# main_pcb.net
KiCad netlist of a schematic drawn in EAGLE
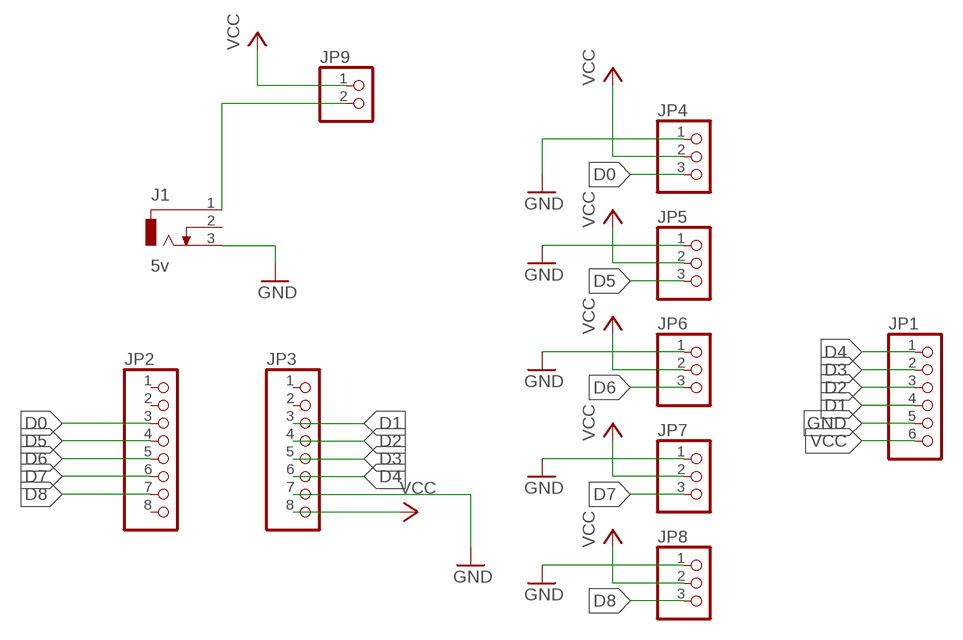
[diagram p0: schematic, sheet 1]

(export (version "E")
  (design (tool "Eeschema 10.0.6"))
  (components
    (comp (ref "J1")
      (value "5v")
      (footprint "eagle-import:DCJ0303")
      (libsource (lib "eagle-import") (part "DCJ0303"))
    )
    (comp (ref "JP1")
      (value "PINHD-1X6")
      (footprint "eagle-import:1X06")
      (libsource (lib "eagle-import") (part "PINHD-1X6"))
    )
    (comp (ref "JP2")
      (value "PINHD-1X8")
      (footprint "eagle-import:1X08")
      (libsource (lib "eagle-import") (part "PINHD-1X8"))
    )
    (comp (ref "JP3")
      (value "PINHD-1X8")
      (footprint "eagle-import:1X08")
      (libsource (lib "eagle-import") (part "PINHD-1X8"))
    )
    (comp (ref "JP4")
      (value "PINHD-1X3")
      (footprint "eagle-import:1X03")
      (libsource (lib "eagle-import") (part "PINHD-1X3"))
    )
    (comp (ref "JP5")
      (value "PINHD-1X3")
      (footprint "eagle-import:1X03")
      (libsource (lib "eagle-import") (part "PINHD-1X3"))
    )
    (comp (ref "JP6")
      (value "PINHD-1X3")
      (footprint "eagle-import:1X03")
      (libsource (lib "eagle-import") (part "PINHD-1X3"))
    )
    (comp (ref "JP7")
      (value "PINHD-1X3")
      (footprint "eagle-import:1X03")
      (libsource (lib "eagle-import") (part "PINHD-1X3"))
    )
    (comp (ref "JP8")
      (value "PINHD-1X3")
      (footprint "eagle-import:1X03")
      (libsource (lib "eagle-import") (part "PINHD-1X3"))
    )
    (comp (ref "JP9")
      (value "PINHD-1X2")
      (footprint "eagle-import:1X02")
      (libsource (lib "eagle-import") (part "PINHD-1X2"))
    )
  )
  (nets
    (net (code "1") (name "D0") (class "Default")
      (node (ref "JP2") (pin "3") (pinfunction "3_3") (pintype "passive"))
      (node (ref "JP4") (pin "3") (pinfunction "3_3") (pintype "passive"))
    )
    (net (code "2") (name "D1") (class "Default")
      (node (ref "JP1") (pin "4") (pinfunction "4_4") (pintype "passive"))
      (node (ref "JP3") (pin "3") (pinfunction "3_3") (pintype "passive"))
    )
    (net (code "3") (name "D2") (class "Default")
      (node (ref "JP1") (pin "3") (pinfunction "3_3") (pintype "passive"))
      (node (ref "JP3") (pin "4") (pinfunction "4_4") (pintype "passive"))
    )
    (net (code "4") (name "D3") (class "Default")
      (node (ref "JP1") (pin "2") (pinfunction "2_2") (pintype "passive"))
      (node (ref "JP3") (pin "5") (pinfunction "5_5") (pintype "passive"))
    )
    (net (code "5") (name "D4") (class "Default")
      (node (ref "JP1") (pin "1") (pinfunction "1_1") (pintype "passive"))
      (node (ref "JP3") (pin "6") (pinfunction "6_6") (pintype "passive"))
    )
    (net (code "6") (name "D5") (class "Default")
      (node (ref "JP2") (pin "4") (pinfunction "4_4") (pintype "passive"))
      (node (ref "JP5") (pin "3") (pinfunction "3_3") (pintype "passive"))
    )
    (net (code "7") (name "D6") (class "Default")
      (node (ref "JP2") (pin "5") (pinfunction "5_5") (pintype "passive"))
      (node (ref "JP6") (pin "3") (pinfunction "3_3") (pintype "passive"))
    )
    (net (code "8") (name "D7") (class "Default")
      (node (ref "JP2") (pin "6") (pinfunction "6_6") (pintype "passive"))
      (node (ref "JP7") (pin "3") (pinfunction "3_3") (pintype "passive"))
    )
    (net (code "9") (name "D8") (class "Default")
      (node (ref "JP2") (pin "7") (pinfunction "7_7") (pintype "passive"))
      (node (ref "JP8") (pin "3") (pinfunction "3_3") (pintype "passive"))
    )
    (net (code "10") (name "GND") (class "Default")
      (node (ref "J1") (pin "3") (pinfunction "3_3") (pintype "passive"))
      (node (ref "JP1") (pin "5") (pinfunction "5_5") (pintype "passive"))
      (node (ref "JP3") (pin "7") (pinfunction "7_7") (pintype "passive"))
      (node (ref "JP4") (pin "1") (pinfunction "1_1") (pintype "passive"))
      (node (ref "JP5") (pin "1") (pinfunction "1_1") (pintype "passive"))
      (node (ref "JP6") (pin "1") (pinfunction "1_1") (pintype "passive"))
      (node (ref "JP7") (pin "1") (pinfunction "1_1") (pintype "passive"))
      (node (ref "JP8") (pin "1") (pinfunction "1_1") (pintype "passive"))
    )
    (net (code "11") (name "Net-(J1-Pad1)") (class "Default")
      (node (ref "J1") (pin "1") (pinfunction "1_1") (pintype "passive"))
      (node (ref "JP9") (pin "2") (pinfunction "2_2") (pintype "passive"))
    )
    (net (code "12") (name "VCC") (class "Default")
      (node (ref "JP1") (pin "6") (pinfunction "6_6") (pintype "passive"))
      (node (ref "JP3") (pin "8") (pinfunction "8_8") (pintype "passive"))
      (node (ref "JP4") (pin "2") (pinfunction "2_2") (pintype "passive"))
      (node (ref "JP5") (pin "2") (pinfunction "2_2") (pintype "passive"))
      (node (ref "JP6") (pin "2") (pinfunction "2_2") (pintype "passive"))
      (node (ref "JP7") (pin "2") (pinfunction "2_2") (pintype "passive"))
      (node (ref "JP8") (pin "2") (pinfunction "2_2") (pintype "passive"))
      (node (ref "JP9") (pin "1") (pinfunction "1_1") (pintype "passive"))
    )
    (net (code "13") (name "unconnected-(J1-Pad2)") (class "Default")
      (node (ref "J1") (pin "2") (pinfunction "2_2") (pintype "passive"))
    )
    (net (code "14") (name "unconnected-(JP2-Pad1)") (class "Default")
      (node (ref "JP2") (pin "1") (pinfunction "1_1") (pintype "passive"))
    )
    (net (code "15") (name "unconnected-(JP2-Pad2)") (class "Default")
      (node (ref "JP2") (pin "2") (pinfunction "2_2") (pintype "passive"))
    )
    (net (code "16") (name "unconnected-(JP2-Pad8)") (class "Default")
      (node (ref "JP2") (pin "8") (pinfunction "8_8") (pintype "passive"))
    )
    (net (code "17") (name "unconnected-(JP3-Pad1)") (class "Default")
      (node (ref "JP3") (pin "1") (pinfunction "1_1") (pintype "passive"))
    )
    (net (code "18") (name "unconnected-(JP3-Pad2)") (class "Default")
      (node (ref "JP3") (pin "2") (pinfunction "2_2") (pintype "passive"))
    )
  )
)
